# WIFI_Module.net
KiCad netlist of a schematic drawn in Altium Designer
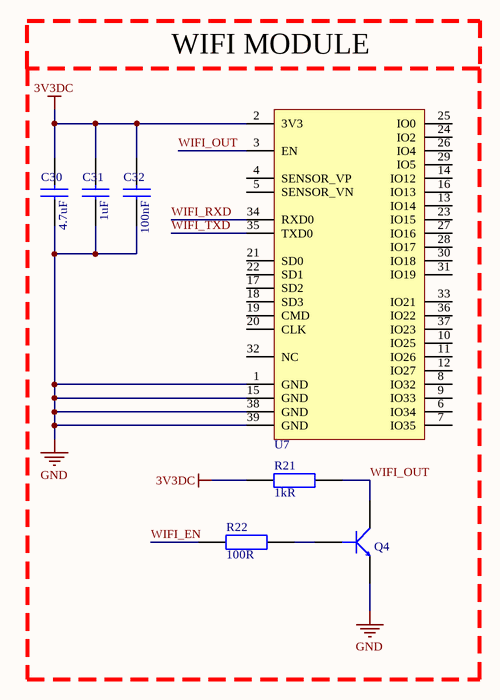
[diagram p0: WIFI Module.SchDoc]

(export (version "E")
  (design (tool "Eeschema 10.0.6"))
  (components
    (comp (ref "C30")
      (value "CL21A475KAQNNNE")
      (footprint "CAP_0805")
      (description "CAP CER 4.7uF %10 0805")
      (fields
        (field (name "MANUFACTURER") "Samsung")
        (field (name "TOLERANCE") "10%")
        (field (name "CAPACITANCE") "4.7uF")
        (field (name "DESIGNED BY") "BERK")
      )
      (libsource (lib "UDEMY_Library") (part "CAP CER 4.7uF 0805"))
    )
    (comp (ref "C31")
      (value "CL21B105KBFNNNE")
      (footprint "CAP_0805")
      (description "CAP CER 1uF %10 0805")
      (fields
        (field (name "MANUFACTURER") "Samsung")
        (field (name "TOLERANCE") "10%")
        (field (name "CAPACITANCE") "1uF")
        (field (name "DESIGNED BY") "BERK")
      )
      (libsource (lib "UDEMY_Library") (part "CAP CER 1uF 0805"))
    )
    (comp (ref "C32")
      (value "CL21B104KBCNNNC")
      (footprint "CAP_0805")
      (description "CAP CER 100nF %10 0805")
      (fields
        (field (name "MANUFACTURER") "Samsung")
        (field (name "TOLERANCE") "10%")
        (field (name "CAPACITANCE") "100nF")
        (field (name "DESIGNED BY") "BERK")
      )
      (libsource (lib "UDEMY_Library") (part "CAP CER 100nF 0805"))
    )
    (comp (ref "Q4")
      (value "MMBT3904-7-F")
      (footprint "SOT-23F")
      (description "Transistor General Purpose BJT NPN 40 Volt 0.2A Automotive 3-Pin SOT-23")
      (fields (field (name "MANUFACTURER") "Diodes Zetex") (field (name "DESIGNED BY") "BERK"))
      (libsource (lib "UDEMY_Library") (part "MMBT3904-7-F"))
    )
    (comp (ref "R21")
      (value "RC0603FR-0710KL")
      (footprint "RES_0603")
      (description "RES 1K %1 OHM 0603 SMD")
      (fields
        (field (name "MANUFACTURER") "Yageo")
        (field (name "MANUFACTURER PART NUMBER") "RC0603JR-071KL")
        (field (name "RESISTANCE") "1kR")
        (field (name "DESIGNED BY") "BERK")
      )
      (libsource (lib "UDEMY_Library") (part "RES 1K OHM 0603"))
    )
    (comp (ref "R22")
      (value "RC0603JR-07100RL")
      (footprint "RES_0603")
      (description "RES 100 %5 OHM 0603 SMD")
      (fields
        (field (name "MANUFACTURER") "Yageo")
        (field (name "TOLERANCE") "5%")
        (field (name "RESISTANCE") "100R")
        (field (name "DESIGNED BY") "BERK")
      )
      (libsource (lib "UDEMY_Library") (part "RES 100 OHM 0603"))
    )
    (comp (ref "U7")
      (value "ESP32-WROOM-32")
      (footprint "ESP32-32")
      (description "SMD MODULE, ESP32-D0WDQ6, 32MBIT")
      (fields (field (name "MANUFACTURER") "Espressif Systems") (field (name "DESIGNED BY") "BERK"))
      (libsource (lib "UDEMY_Library") (part "ESP32-WROOM-32"))
    )
  )
  (nets
    (net (code "1") (name "/WIFI_EN") (class "Default")
      (node (ref "R22") (pin "1") (pinfunction "1_1") (pintype "passive"))
    )
    (net (code "2") (name "/WIFI_OUT") (class "Default")
      (node (ref "Q4") (pin "3") (pinfunction "C_3") (pintype "power_in"))
      (node (ref "R21") (pin "2") (pinfunction "2_2") (pintype "passive"))
      (node (ref "U7") (pin "3") (pinfunction "EN_3") (pintype "passive"))
    )
    (net (code "3") (name "/WIFI_RXD") (class "Default")
      (node (ref "U7") (pin "34") (pinfunction "RXD0_34") (pintype "passive"))
    )
    (net (code "4") (name "/WIFI_TXD") (class "Default")
      (node (ref "U7") (pin "35") (pinfunction "TXD0_35") (pintype "passive"))
    )
    (net (code "5") (name "3V3DC") (class "Default")
      (node (ref "C30") (pin "2") (pinfunction "2_2") (pintype "passive"))
      (node (ref "C31") (pin "2") (pinfunction "2_2") (pintype "passive"))
      (node (ref "C32") (pin "2") (pinfunction "2_2") (pintype "passive"))
      (node (ref "R21") (pin "1") (pinfunction "1_1") (pintype "passive"))
      (node (ref "U7") (pin "2") (pinfunction "3V3_2") (pintype "passive"))
    )
    (net (code "6") (name "GND") (class "Default")
      (node (ref "C30") (pin "1") (pinfunction "1_1") (pintype "passive"))
      (node (ref "C31") (pin "1") (pinfunction "1_1") (pintype "passive"))
      (node (ref "C32") (pin "1") (pinfunction "1_1") (pintype "passive"))
      (node (ref "Q4") (pin "2") (pinfunction "E_2") (pintype "power_in"))
      (node (ref "U7") (pin "1") (pinfunction "GND_1") (pintype "passive"))
      (node (ref "U7") (pin "15") (pinfunction "GND_15") (pintype "passive"))
      (node (ref "U7") (pin "38") (pinfunction "GND_38") (pintype "passive"))
      (node (ref "U7") (pin "39") (pinfunction "GND_39") (pintype "passive"))
    )
    (net (code "7") (name "Net-(Q4-B)") (class "Default")
      (node (ref "Q4") (pin "1") (pinfunction "B_1") (pintype "power_in"))
      (node (ref "R22") (pin "2") (pinfunction "2_2") (pintype "passive"))
    )
    (net (code "8") (name "unconnected-(U7-CLK-Pad20)") (class "Default")
      (node (ref "U7") (pin "20") (pinfunction "CLK_20") (pintype "passive"))
    )
    (net (code "9") (name "unconnected-(U7-CMD-Pad19)") (class "Default")
      (node (ref "U7") (pin "19") (pinfunction "CMD_19") (pintype "passive"))
    )
    (net (code "10") (name "unconnected-(U7-IO0-Pad25)") (class "Default")
      (node (ref "U7") (pin "25") (pinfunction "IO0_25") (pintype "passive"))
    )
    (net (code "11") (name "unconnected-(U7-IO2-Pad24)") (class "Default")
      (node (ref "U7") (pin "24") (pinfunction "IO2_24") (pintype "passive"))
    )
    (net (code "12") (name "unconnected-(U7-IO4-Pad26)") (class "Default")
      (node (ref "U7") (pin "26") (pinfunction "IO4_26") (pintype "passive"))
    )
    (net (code "13") (name "unconnected-(U7-IO5-Pad29)") (class "Default")
      (node (ref "U7") (pin "29") (pinfunction "IO5_29") (pintype "passive"))
    )
    (net (code "14") (name "unconnected-(U7-IO12-Pad14)") (class "Default")
      (node (ref "U7") (pin "14") (pinfunction "IO12_14") (pintype "passive"))
    )
    (net (code "15") (name "unconnected-(U7-IO13-Pad16)") (class "Default")
      (node (ref "U7") (pin "16") (pinfunction "IO13_16") (pintype "passive"))
    )
    (net (code "16") (name "unconnected-(U7-IO14-Pad13)") (class "Default")
      (node (ref "U7") (pin "13") (pinfunction "IO14_13") (pintype "passive"))
    )
    (net (code "17") (name "unconnected-(U7-IO15-Pad23)") (class "Default")
      (node (ref "U7") (pin "23") (pinfunction "IO15_23") (pintype "passive"))
    )
    (net (code "18") (name "unconnected-(U7-IO16-Pad27)") (class "Default")
      (node (ref "U7") (pin "27") (pinfunction "IO16_27") (pintype "passive"))
    )
    (net (code "19") (name "unconnected-(U7-IO17-Pad28)") (class "Default")
      (node (ref "U7") (pin "28") (pinfunction "IO17_28") (pintype "passive"))
    )
    (net (code "20") (name "unconnected-(U7-IO18-Pad30)") (class "Default")
      (node (ref "U7") (pin "30") (pinfunction "IO18_30") (pintype "passive"))
    )
    (net (code "21") (name "unconnected-(U7-IO19-Pad31)") (class "Default")
      (node (ref "U7") (pin "31") (pinfunction "IO19_31") (pintype "passive"))
    )
    (net (code "22") (name "unconnected-(U7-IO21-Pad33)") (class "Default")
      (node (ref "U7") (pin "33") (pinfunction "IO21_33") (pintype "passive"))
    )
    (net (code "23") (name "unconnected-(U7-IO22-Pad36)") (class "Default")
      (node (ref "U7") (pin "36") (pinfunction "IO22_36") (pintype "passive"))
    )
    (net (code "24") (name "unconnected-(U7-IO23-Pad37)") (class "Default")
      (node (ref "U7") (pin "37") (pinfunction "IO23_37") (pintype "passive"))
    )
    (net (code "25") (name "unconnected-(U7-IO25-Pad10)") (class "Default")
      (node (ref "U7") (pin "10") (pinfunction "IO25_10") (pintype "passive"))
    )
    (net (code "26") (name "unconnected-(U7-IO26-Pad11)") (class "Default")
      (node (ref "U7") (pin "11") (pinfunction "IO26_11") (pintype "passive"))
    )
    (net (code "27") (name "unconnected-(U7-IO27-Pad12)") (class "Default")
      (node (ref "U7") (pin "12") (pinfunction "IO27_12") (pintype "passive"))
    )
    (net (code "28") (name "unconnected-(U7-IO32-Pad8)") (class "Default")
      (node (ref "U7") (pin "8") (pinfunction "IO32_8") (pintype "passive"))
    )
    (net (code "29") (name "unconnected-(U7-IO33-Pad9)") (class "Default")
      (node (ref "U7") (pin "9") (pinfunction "IO33_9") (pintype "passive"))
    )
    (net (code "30") (name "unconnected-(U7-IO34-Pad6)") (class "Default")
      (node (ref "U7") (pin "6") (pinfunction "IO34_6") (pintype "passive"))
    )
    (net (code "31") (name "unconnected-(U7-IO35-Pad7)") (class "Default")
      (node (ref "U7") (pin "7") (pinfunction "IO35_7") (pintype "passive"))
    )
    (net (code "32") (name "unconnected-(U7-NC-Pad32)") (class "Default")
      (node (ref "U7") (pin "32") (pinfunction "NC_32") (pintype "passive"))
    )
    (net (code "33") (name "unconnected-(U7-SD0-Pad21)") (class "Default")
      (node (ref "U7") (pin "21") (pinfunction "SD0_21") (pintype "passive"))
    )
    (net (code "34") (name "unconnected-(U7-SD1-Pad22)") (class "Default")
      (node (ref "U7") (pin "22") (pinfunction "SD1_22") (pintype "passive"))
    )
    (net (code "35") (name "unconnected-(U7-SD2-Pad17)") (class "Default")
      (node (ref "U7") (pin "17") (pinfunction "SD2_17") (pintype "passive"))
    )
    (net (code "36") (name "unconnected-(U7-SD3-Pad18)") (class "Default")
      (node (ref "U7") (pin "18") (pinfunction "SD3_18") (pintype "passive"))
    )
    (net (code "37") (name "unconnected-(U7-SENSOR_VN-Pad5)") (class "Default")
      (node (ref "U7") (pin "5") (pinfunction "SENSOR_VN_5") (pintype "passive"))
    )
    (net (code "38") (name "unconnected-(U7-SENSOR_VP-Pad4)") (class "Default")
      (node (ref "U7") (pin "4") (pinfunction "SENSOR_VP_4") (pintype "passive"))
    )
  )
)
